# Microcontroller.net
KiCad netlist of a schematic drawn in Altium Designer
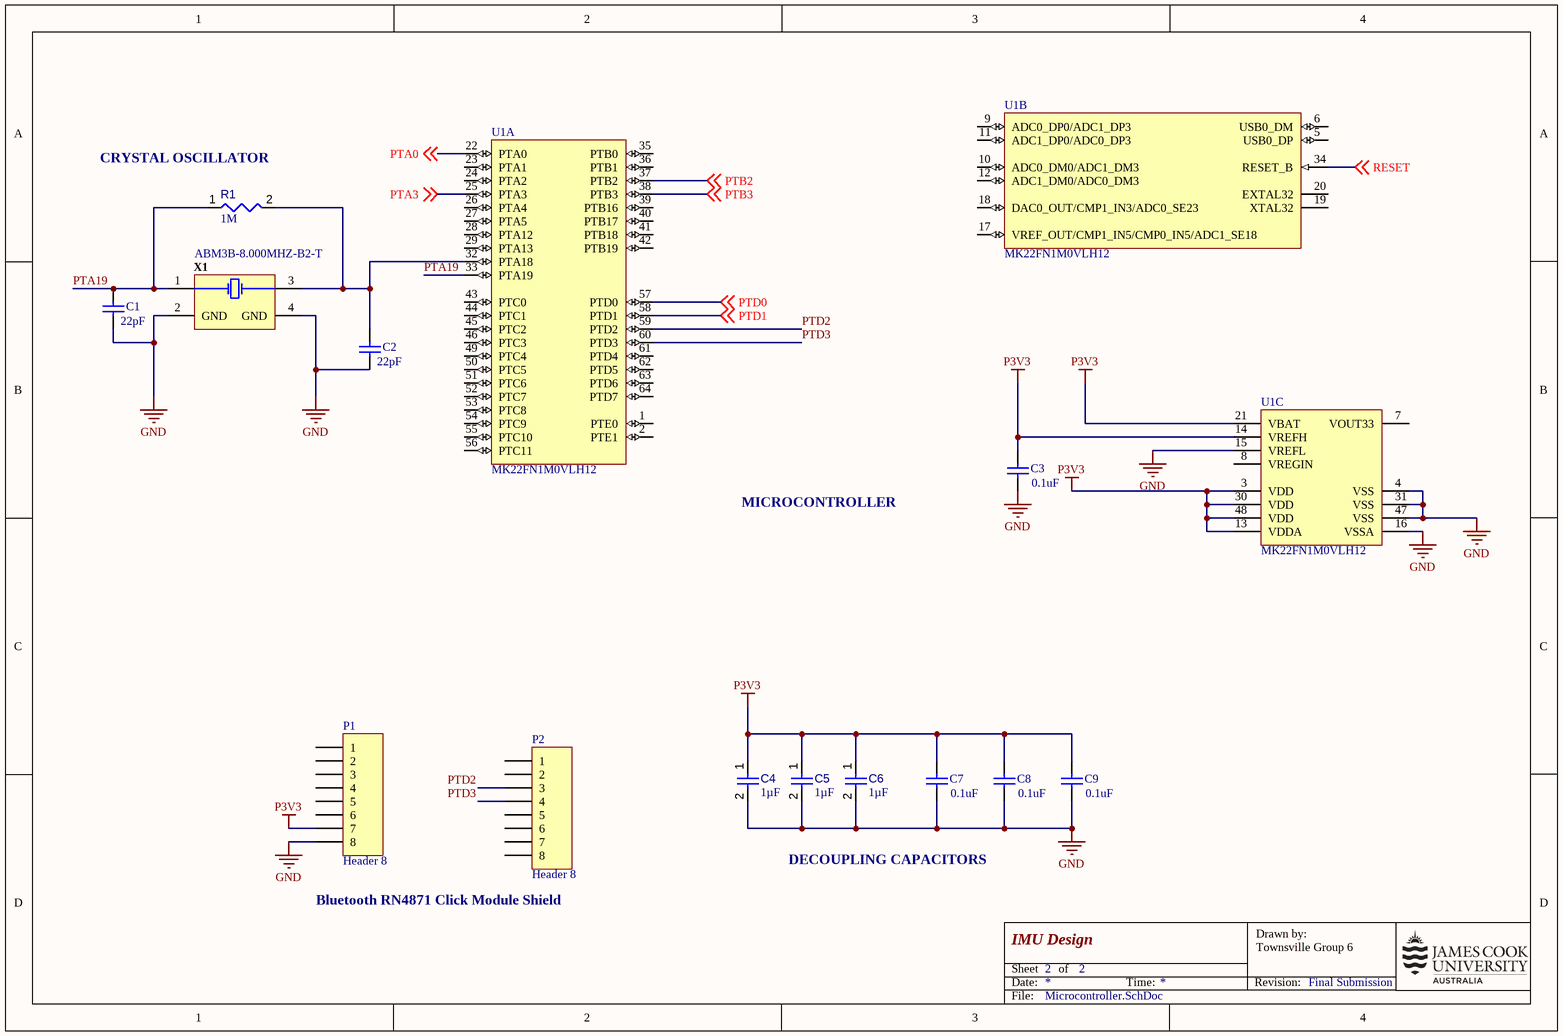
[diagram p0: Microcontroller.SchDoc]

(export (version "E")
  (design (tool "Eeschema 10.0.6"))
  (components
    (comp (ref "C1")
      (value "22pF")
      (footprint "CAPC1206(3216)100_N")
      (description "CAP 22pF 50V ±1% 1206 (3216 Metric) Thickness 1mm SMD")
      (fields (field (name "TOLERANCE") "Â±1%"))
      (libsource (lib "Altium Content Vault") (part "CAP"))
    )
    (comp (ref "C2")
      (value "22pF")
      (footprint "CAPC1206(3216)100_N")
      (description "CAP 22pF 50V ±1% 1206 (3216 Metric) Thickness 1mm SMD")
      (fields (field (name "TOLERANCE") "Â±1%"))
      (libsource (lib "Altium Content Vault") (part "CAP"))
    )
    (comp (ref "C3")
      (value "0.1uF")
      (footprint "CAPC3216X95X55NL15T25")
      (description "Chip Capacitor, 0.1 uF, +/- 10%, 50 V, -55 to 125 degC, 1206 (3216 Metric), RoHS, Tape and Reel")
      (fields (field (name "MANUFACTURER") "Murata"))
      (libsource (lib "Altium Content Vault") (part "CAP-NP-2"))
    )
    (comp (ref "C4")
      (value "1µF")
      (footprint "CAPC3216X180X20ML20")
      (description "Chip Capacitor, 1 uF, +/- 10%, 25 V, 1206 (3216 Metric)")
      (fields (field (name "TOLERANCE") "10%") (field (name "Comment") "Capacitor 1 uF +/- 10% 25 V 1206"))
      (libsource (lib "James Cook University") (part "CAP-NP-2"))
    )
    (comp (ref "C5")
      (value "1µF")
      (footprint "CAPC3216X180X20ML20")
      (description "Chip Capacitor, 1 uF, +/- 10%, 25 V, 1206 (3216 Metric)")
      (fields (field (name "TOLERANCE") "10%") (field (name "Comment") "Capacitor 1 uF +/- 10% 25 V 1206"))
      (libsource (lib "James Cook University") (part "CAP-NP-2"))
    )
    (comp (ref "C6")
      (value "1µF")
      (footprint "CAPC3216X180X20ML20")
      (description "Chip Capacitor, 1 uF, +/- 10%, 25 V, 1206 (3216 Metric)")
      (fields (field (name "TOLERANCE") "10%") (field (name "Comment") "Capacitor 1 uF +/- 10% 25 V 1206"))
      (libsource (lib "James Cook University") (part "CAP-NP-2"))
    )
    (comp (ref "C7")
      (value "0.1uF")
      (footprint "CAPC3216X95X55NL15T25")
      (description "Chip Capacitor, 0.1 uF, +/- 10%, 50 V, -55 to 125 degC, 1206 (3216 Metric), RoHS, Tape and Reel")
      (fields (field (name "MANUFACTURER") "Murata"))
      (libsource (lib "Altium Content Vault") (part "CAP-NP-2"))
    )
    (comp (ref "C8")
      (value "0.1uF")
      (footprint "CAPC3216X95X55NL15T25")
      (description "Chip Capacitor, 0.1 uF, +/- 10%, 50 V, -55 to 125 degC, 1206 (3216 Metric), RoHS, Tape and Reel")
      (fields (field (name "MANUFACTURER") "Murata"))
      (libsource (lib "Altium Content Vault") (part "CAP-NP-2"))
    )
    (comp (ref "C9")
      (value "0.1uF")
      (footprint "CAPC3216X95X55NL15T25")
      (description "Chip Capacitor, 0.1 uF, +/- 10%, 50 V, -55 to 125 degC, 1206 (3216 Metric), RoHS, Tape and Reel")
      (fields (field (name "MANUFACTURER") "Murata"))
      (libsource (lib "Altium Content Vault") (part "CAP-NP-2"))
    )
    (comp (ref "P1")
      (value "Header 8")
      (footprint "HDR1X8")
      (description "Header, 8-Pin")
      (fields (field (name "PUBLISHER") "Altium Limited"))
      (libsource (lib "Miscellaneous Connectors") (part "Header 8"))
    )
    (comp (ref "P2")
      (value "Header 8")
      (footprint "HDR1X8")
      (description "Header, 8-Pin")
      (fields (field (name "PUBLISHER") "Altium Limited"))
      (libsource (lib "Miscellaneous Connectors") (part "Header 8"))
    )
    (comp (ref "R1")
      (value "1M")
      (footprint "RESA60-630X240")
      (description "Axial Resistor, 1 MOhm, +/- 1%, 250 mW, -55 to 155 degC, 2-Pin THD, RoHS, Bulk")
      (fields (field (name "MANUFACTURER") "Yageo") (field (name "TOLERANCE") "1%"))
      (libsource (lib "James Cook University") (part "RES-2"))
    )
    (comp (ref "U1")
      (value "MK22FN1M0VLH12")
      (footprint "FREE-LQFP-64_M")
      (fields (field (name "MANUFACTURER") "Freescale"))
      (libsource (lib "James Cook University") (part "FREE-MK22FN1M0VLH12-LQFP-64"))
    )
    (comp (ref "X1")
      (value "ABM3B-8.000MHZ-B2-T")
      (footprint "ABRA-ABM3B_V")
      (description "Ceramic SMD Crystal, 8 MHz, +/- 20 ppm, 18 pF, -20 to 70 degC, 4-Pin SMD, RoHS, Tape and Reel")
      (fields (field (name "TOLERANCE") "20ppm") (field (name "MANUFACTURER") "Abracon"))
      (libsource (lib "James Cook University") (part "XTAL-1-3-4"))
    )
  )
  (nets
    (net (code "1") (name "/PTA19") (class "Default")
      (node (ref "C1") (pin "2") (pinfunction "2_2") (pintype "passive"))
      (node (ref "R1") (pin "1") (pinfunction "1_1") (pintype "passive"))
      (node (ref "U1") (pin "33") (pinfunction "PTA19_33") (pintype "bidirectional"))
      (node (ref "X1") (pin "1") (pinfunction "X1_1") (pintype "passive"))
    )
    (net (code "2") (name "/PTD2") (class "Default")
      (node (ref "P2") (pin "3") (pinfunction "3_3") (pintype "passive"))
      (node (ref "U1") (pin "59") (pinfunction "PTD2_59") (pintype "bidirectional"))
    )
    (net (code "3") (name "/PTD3") (class "Default")
      (node (ref "P2") (pin "4") (pinfunction "4_4") (pintype "passive"))
      (node (ref "U1") (pin "60") (pinfunction "PTD3_60") (pintype "bidirectional"))
    )
    (net (code "4") (name "GND") (class "Default")
      (node (ref "C1") (pin "1") (pinfunction "1_1") (pintype "passive"))
      (node (ref "C2") (pin "1") (pinfunction "1_1") (pintype "passive"))
      (node (ref "C3") (pin "2") (pinfunction "2_2") (pintype "passive"))
      (node (ref "C4") (pin "2") (pinfunction "2_2") (pintype "passive"))
      (node (ref "C5") (pin "2") (pinfunction "2_2") (pintype "passive"))
      (node (ref "C6") (pin "2") (pinfunction "2_2") (pintype "passive"))
      (node (ref "C7") (pin "1") (pinfunction "1_1") (pintype "passive"))
      (node (ref "C8") (pin "2") (pinfunction "2_2") (pintype "passive"))
      (node (ref "C9") (pin "2") (pinfunction "2_2") (pintype "passive"))
      (node (ref "P1") (pin "8") (pinfunction "8_8") (pintype "passive"))
      (node (ref "U1") (pin "15") (pinfunction "VREFL_15") (pintype "power_in"))
      (node (ref "U1") (pin "16") (pinfunction "VSSA_16") (pintype "power_in"))
      (node (ref "U1") (pin "31") (pinfunction "VSS_31") (pintype "power_in"))
      (node (ref "U1") (pin "4") (pinfunction "VSS_4") (pintype "power_in"))
      (node (ref "U1") (pin "47") (pinfunction "VSS_47") (pintype "power_in"))
      (node (ref "X1") (pin "2") (pinfunction "GND_2") (pintype "power_in"))
      (node (ref "X1") (pin "4") (pinfunction "GND_4") (pintype "power_in"))
    )
    (net (code "5") (name "Net-(U1A-PTA18)") (class "Default")
      (node (ref "C2") (pin "2") (pinfunction "2_2") (pintype "passive"))
      (node (ref "R1") (pin "2") (pinfunction "2_2") (pintype "passive"))
      (node (ref "U1") (pin "32") (pinfunction "PTA18_32") (pintype "bidirectional"))
      (node (ref "X1") (pin "3") (pinfunction "X2_3") (pintype "passive"))
    )
    (net (code "6") (name "P3V3") (class "Default")
      (node (ref "C3") (pin "1") (pinfunction "1_1") (pintype "passive"))
      (node (ref "C4") (pin "1") (pinfunction "1_1") (pintype "passive"))
      (node (ref "C5") (pin "1") (pinfunction "1_1") (pintype "passive"))
      (node (ref "C6") (pin "1") (pinfunction "1_1") (pintype "passive"))
      (node (ref "C7") (pin "2") (pinfunction "2_2") (pintype "passive"))
      (node (ref "C8") (pin "1") (pinfunction "1_1") (pintype "passive"))
      (node (ref "C9") (pin "1") (pinfunction "1_1") (pintype "passive"))
      (node (ref "P1") (pin "7") (pinfunction "7_7") (pintype "passive"))
      (node (ref "U1") (pin "13") (pinfunction "VDDA_13") (pintype "power_in"))
      (node (ref "U1") (pin "14") (pinfunction "VREFH_14") (pintype "power_in"))
      (node (ref "U1") (pin "21") (pinfunction "VBAT_21") (pintype "power_in"))
      (node (ref "U1") (pin "3") (pinfunction "VDD_3") (pintype "power_in"))
      (node (ref "U1") (pin "30") (pinfunction "VDD_30") (pintype "power_in"))
      (node (ref "U1") (pin "48") (pinfunction "VDD_48") (pintype "power_in"))
    )
    (net (code "7") (name "PTA0") (class "Default")
      (node (ref "U1") (pin "22") (pinfunction "PTA0_22") (pintype "bidirectional"))
    )
    (net (code "8") (name "PTA3") (class "Default")
      (node (ref "U1") (pin "25") (pinfunction "PTA3_25") (pintype "bidirectional"))
    )
    (net (code "9") (name "PTB2") (class "Default")
      (node (ref "U1") (pin "37") (pinfunction "PTB2_37") (pintype "bidirectional"))
    )
    (net (code "10") (name "PTB3") (class "Default")
      (node (ref "U1") (pin "38") (pinfunction "PTB3_38") (pintype "bidirectional"))
    )
    (net (code "11") (name "PTD0") (class "Default")
      (node (ref "U1") (pin "57") (pinfunction "PTD0_57") (pintype "bidirectional"))
    )
    (net (code "12") (name "PTD1") (class "Default")
      (node (ref "U1") (pin "58") (pinfunction "PTD1_58") (pintype "bidirectional"))
    )
    (net (code "13") (name "RESET") (class "Default")
      (node (ref "U1") (pin "34") (pinfunction "RESET_B_34") (pintype "input"))
    )
    (net (code "14") (name "unconnected-(P1-Pad1)") (class "Default")
      (node (ref "P1") (pin "1") (pinfunction "1_1") (pintype "passive"))
    )
    (net (code "15") (name "unconnected-(P1-Pad2)") (class "Default")
      (node (ref "P1") (pin "2") (pinfunction "2_2") (pintype "passive"))
    )
    (net (code "16") (name "unconnected-(P1-Pad3)") (class "Default")
      (node (ref "P1") (pin "3") (pinfunction "3_3") (pintype "passive"))
    )
    (net (code "17") (name "unconnected-(P1-Pad4)") (class "Default")
      (node (ref "P1") (pin "4") (pinfunction "4_4") (pintype "passive"))
    )
    (net (code "18") (name "unconnected-(P1-Pad5)") (class "Default")
      (node (ref "P1") (pin "5") (pinfunction "5_5") (pintype "passive"))
    )
    (net (code "19") (name "unconnected-(P1-Pad6)") (class "Default")
      (node (ref "P1") (pin "6") (pinfunction "6_6") (pintype "passive"))
    )
    (net (code "20") (name "unconnected-(P2-Pad1)") (class "Default")
      (node (ref "P2") (pin "1") (pinfunction "1_1") (pintype "passive"))
    )
    (net (code "21") (name "unconnected-(P2-Pad2)") (class "Default")
      (node (ref "P2") (pin "2") (pinfunction "2_2") (pintype "passive"))
    )
    (net (code "22") (name "unconnected-(P2-Pad5)") (class "Default")
      (node (ref "P2") (pin "5") (pinfunction "5_5") (pintype "passive"))
    )
    (net (code "23") (name "unconnected-(P2-Pad6)") (class "Default")
      (node (ref "P2") (pin "6") (pinfunction "6_6") (pintype "passive"))
    )
    (net (code "24") (name "unconnected-(P2-Pad7)") (class "Default")
      (node (ref "P2") (pin "7") (pinfunction "7_7") (pintype "passive"))
    )
    (net (code "25") (name "unconnected-(P2-Pad8)") (class "Default")
      (node (ref "P2") (pin "8") (pinfunction "8_8") (pintype "passive"))
    )
    (net (code "26") (name "unconnected-(U1A-PTA1-Pad23)") (class "Default")
      (node (ref "U1") (pin "23") (pinfunction "PTA1_23") (pintype "bidirectional"))
    )
    (net (code "27") (name "unconnected-(U1A-PTA2-Pad24)") (class "Default")
      (node (ref "U1") (pin "24") (pinfunction "PTA2_24") (pintype "bidirectional"))
    )
    (net (code "28") (name "unconnected-(U1A-PTA4-Pad26)") (class "Default")
      (node (ref "U1") (pin "26") (pinfunction "PTA4_26") (pintype "bidirectional"))
    )
    (net (code "29") (name "unconnected-(U1A-PTA5-Pad27)") (class "Default")
      (node (ref "U1") (pin "27") (pinfunction "PTA5_27") (pintype "bidirectional"))
    )
    (net (code "30") (name "unconnected-(U1A-PTA12-Pad28)") (class "Default")
      (node (ref "U1") (pin "28") (pinfunction "PTA12_28") (pintype "bidirectional"))
    )
    (net (code "31") (name "unconnected-(U1A-PTA13-Pad29)") (class "Default")
      (node (ref "U1") (pin "29") (pinfunction "PTA13_29") (pintype "bidirectional"))
    )
    (net (code "32") (name "unconnected-(U1A-PTB0-Pad35)") (class "Default")
      (node (ref "U1") (pin "35") (pinfunction "PTB0_35") (pintype "bidirectional"))
    )
    (net (code "33") (name "unconnected-(U1A-PTB1-Pad36)") (class "Default")
      (node (ref "U1") (pin "36") (pinfunction "PTB1_36") (pintype "bidirectional"))
    )
    (net (code "34") (name "unconnected-(U1A-PTB16-Pad39)") (class "Default")
      (node (ref "U1") (pin "39") (pinfunction "PTB16_39") (pintype "bidirectional"))
    )
    (net (code "35") (name "unconnected-(U1A-PTB17-Pad40)") (class "Default")
      (node (ref "U1") (pin "40") (pinfunction "PTB17_40") (pintype "bidirectional"))
    )
    (net (code "36") (name "unconnected-(U1A-PTB18-Pad41)") (class "Default")
      (node (ref "U1") (pin "41") (pinfunction "PTB18_41") (pintype "bidirectional"))
    )
    (net (code "37") (name "unconnected-(U1A-PTB19-Pad42)") (class "Default")
      (node (ref "U1") (pin "42") (pinfunction "PTB19_42") (pintype "bidirectional"))
    )
    (net (code "38") (name "unconnected-(U1A-PTC0-Pad43)") (class "Default")
      (node (ref "U1") (pin "43") (pinfunction "PTC0_43") (pintype "bidirectional"))
    )
    (net (code "39") (name "unconnected-(U1A-PTC1-Pad44)") (class "Default")
      (node (ref "U1") (pin "44") (pinfunction "PTC1_44") (pintype "bidirectional"))
    )
    (net (code "40") (name "unconnected-(U1A-PTC2-Pad45)") (class "Default")
      (node (ref "U1") (pin "45") (pinfunction "PTC2_45") (pintype "bidirectional"))
    )
    (net (code "41") (name "unconnected-(U1A-PTC3-Pad46)") (class "Default")
      (node (ref "U1") (pin "46") (pinfunction "PTC3_46") (pintype "bidirectional"))
    )
    (net (code "42") (name "unconnected-(U1A-PTC4-Pad49)") (class "Default")
      (node (ref "U1") (pin "49") (pinfunction "PTC4_49") (pintype "bidirectional"))
    )
    (net (code "43") (name "unconnected-(U1A-PTC5-Pad50)") (class "Default")
      (node (ref "U1") (pin "50") (pinfunction "PTC5_50") (pintype "bidirectional"))
    )
    (net (code "44") (name "unconnected-(U1A-PTC6-Pad51)") (class "Default")
      (node (ref "U1") (pin "51") (pinfunction "PTC6_51") (pintype "bidirectional"))
    )
    (net (code "45") (name "unconnected-(U1A-PTC7-Pad52)") (class "Default")
      (node (ref "U1") (pin "52") (pinfunction "PTC7_52") (pintype "bidirectional"))
    )
    (net (code "46") (name "unconnected-(U1A-PTC8-Pad53)") (class "Default")
      (node (ref "U1") (pin "53") (pinfunction "PTC8_53") (pintype "bidirectional"))
    )
    (net (code "47") (name "unconnected-(U1A-PTC9-Pad54)") (class "Default")
      (node (ref "U1") (pin "54") (pinfunction "PTC9_54") (pintype "bidirectional"))
    )
    (net (code "48") (name "unconnected-(U1A-PTC10-Pad55)") (class "Default")
      (node (ref "U1") (pin "55") (pinfunction "PTC10_55") (pintype "bidirectional"))
    )
    (net (code "49") (name "unconnected-(U1A-PTC11-Pad56)") (class "Default")
      (node (ref "U1") (pin "56") (pinfunction "PTC11_56") (pintype "bidirectional"))
    )
    (net (code "50") (name "unconnected-(U1A-PTD4-Pad61)") (class "Default")
      (node (ref "U1") (pin "61") (pinfunction "PTD4_61") (pintype "bidirectional"))
    )
    (net (code "51") (name "unconnected-(U1A-PTD5-Pad62)") (class "Default")
      (node (ref "U1") (pin "62") (pinfunction "PTD5_62") (pintype "bidirectional"))
    )
    (net (code "52") (name "unconnected-(U1A-PTD6-Pad63)") (class "Default")
      (node (ref "U1") (pin "63") (pinfunction "PTD6_63") (pintype "bidirectional"))
    )
    (net (code "53") (name "unconnected-(U1A-PTD7-Pad64)") (class "Default")
      (node (ref "U1") (pin "64") (pinfunction "PTD7_64") (pintype "bidirectional"))
    )
    (net (code "54") (name "unconnected-(U1A-PTE0-Pad1)") (class "Default")
      (node (ref "U1") (pin "1") (pinfunction "PTE0_1") (pintype "bidirectional"))
    )
    (net (code "55") (name "unconnected-(U1A-PTE1-Pad2)") (class "Default")
      (node (ref "U1") (pin "2") (pinfunction "PTE1_2") (pintype "bidirectional"))
    )
    (net (code "56") (name "unconnected-(U1B-ADC0_DM0{slash}ADC1_DM3-Pad10)") (class "Default")
      (node (ref "U1") (pin "10") (pinfunction "ADC0_DM0/ADC1_DM3_10") (pintype "bidirectional"))
    )
    (net (code "57") (name "unconnected-(U1B-ADC0_DP0{slash}ADC1_DP3-Pad9)") (class "Default")
      (node (ref "U1") (pin "9") (pinfunction "ADC0_DP0/ADC1_DP3_9") (pintype "bidirectional"))
    )
    (net (code "58") (name "unconnected-(U1B-ADC1_DM0{slash}ADC0_DM3-Pad12)") (class "Default")
      (node (ref "U1") (pin "12") (pinfunction "ADC1_DM0/ADC0_DM3_12") (pintype "bidirectional"))
    )
    (net (code "59") (name "unconnected-(U1B-ADC1_DP0{slash}ADC0_DP3-Pad11)") (class "Default")
      (node (ref "U1") (pin "11") (pinfunction "ADC1_DP0/ADC0_DP3_11") (pintype "bidirectional"))
    )
    (net (code "60") (name "unconnected-(U1B-DAC0_OUT{slash}CMP1_IN3{slash}ADC0_SE23-Pad18)") (class "Default")
      (node (ref "U1") (pin "18") (pinfunction "DAC0_OUT/CMP1_IN3/ADC0_SE23_18") (pintype "bidirectional"))
    )
    (net (code "61") (name "unconnected-(U1B-EXTAL32-Pad20)") (class "Default")
      (node (ref "U1") (pin "20") (pinfunction "EXTAL32_20") (pintype "passive"))
    )
    (net (code "62") (name "unconnected-(U1B-USB0_DM-Pad6)") (class "Default")
      (node (ref "U1") (pin "6") (pinfunction "USB0_DM_6") (pintype "bidirectional"))
    )
    (net (code "63") (name "unconnected-(U1B-USB0_DP-Pad5)") (class "Default")
      (node (ref "U1") (pin "5") (pinfunction "USB0_DP_5") (pintype "bidirectional"))
    )
    (net (code "64") (name "unconnected-(U1B-VREF_OUT{slash}CMP1_IN5{slash}CMP0_IN5{slash}ADC1_SE18-Pad17)") (class "Default")
      (node (ref "U1") (pin "17") (pinfunction "VREF_OUT/CMP1_IN5/CMP0_IN5/ADC1_SE18_17") (pintype "bidirectional"))
    )
    (net (code "65") (name "unconnected-(U1B-XTAL32-Pad19)") (class "Default")
      (node (ref "U1") (pin "19") (pinfunction "XTAL32_19") (pintype "passive"))
    )
    (net (code "66") (name "unconnected-(U1C-VOUT33-Pad7)") (class "Default")
      (node (ref "U1") (pin "7") (pinfunction "VOUT33_7") (pintype "power_in"))
    )
    (net (code "67") (name "unconnected-(U1C-VREGIN-Pad8)") (class "Default")
      (node (ref "U1") (pin "8") (pinfunction "VREGIN_8") (pintype "power_in"))
    )
  )
)
